# PRY397.net
KiCad netlist of a schematic drawn in EAGLE
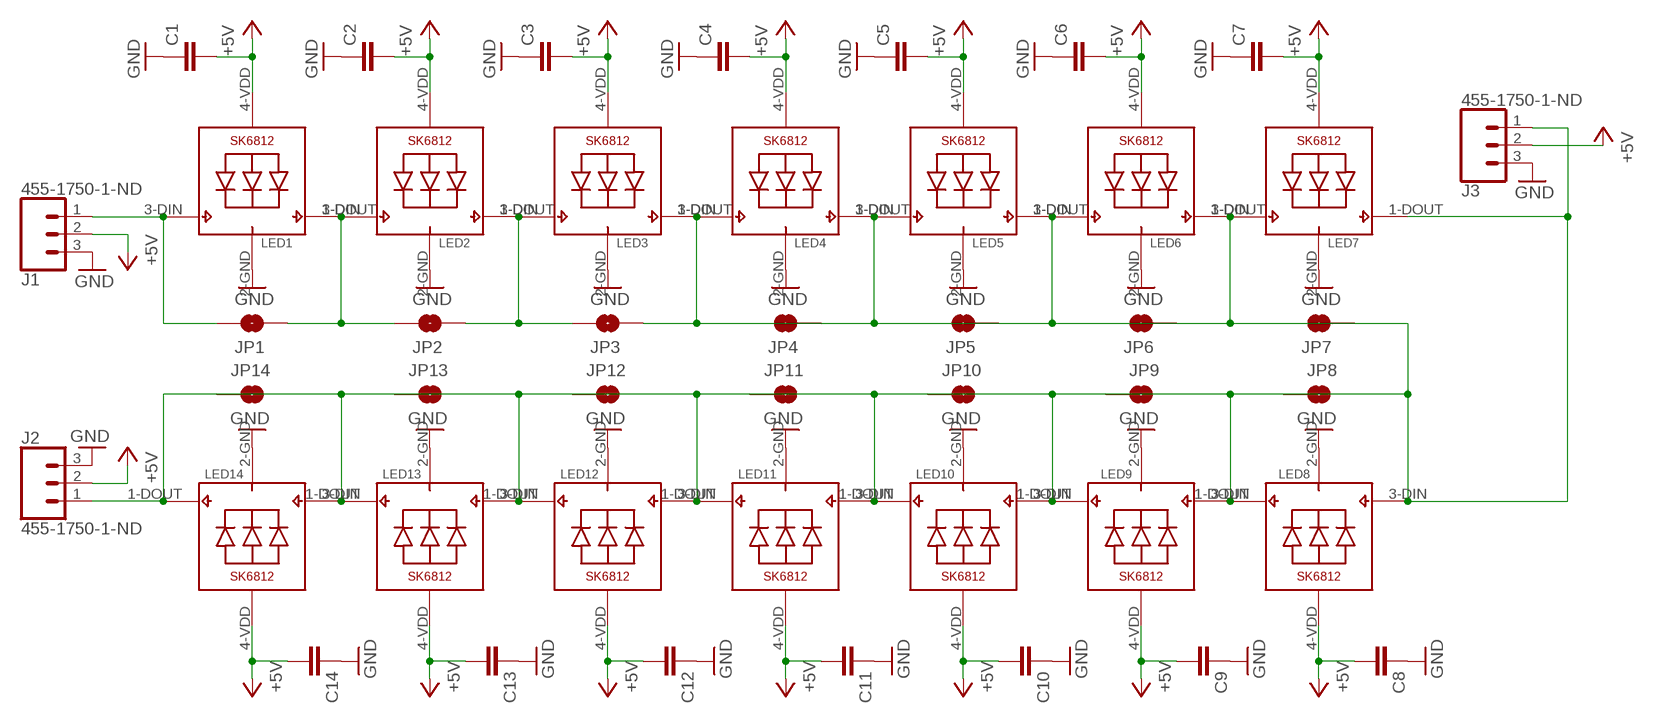
[diagram p0: schematic, sheet 1]

(export (version "E")
  (design (tool "Eeschema 10.0.6"))
  (components
    (comp (ref "C1")
      (value "C-EUC1206")
      (footprint "eagle-import:C1206")
      (libsource (lib "eagle-import") (part "C-EUC1206"))
    )
    (comp (ref "C2")
      (value "C-EUC1206")
      (footprint "eagle-import:C1206")
      (libsource (lib "eagle-import") (part "C-EUC1206"))
    )
    (comp (ref "C3")
      (value "C-EUC1206")
      (footprint "eagle-import:C1206")
      (libsource (lib "eagle-import") (part "C-EUC1206"))
    )
    (comp (ref "C4")
      (value "C-EUC1206")
      (footprint "eagle-import:C1206")
      (libsource (lib "eagle-import") (part "C-EUC1206"))
    )
    (comp (ref "C5")
      (value "C-EUC1206")
      (footprint "eagle-import:C1206")
      (libsource (lib "eagle-import") (part "C-EUC1206"))
    )
    (comp (ref "C6")
      (value "C-EUC1206")
      (footprint "eagle-import:C1206")
      (libsource (lib "eagle-import") (part "C-EUC1206"))
    )
    (comp (ref "C7")
      (value "C-EUC1206")
      (footprint "eagle-import:C1206")
      (libsource (lib "eagle-import") (part "C-EUC1206"))
    )
    (comp (ref "C8")
      (value "C-EUC1206")
      (footprint "eagle-import:C1206")
      (libsource (lib "eagle-import") (part "C-EUC1206"))
    )
    (comp (ref "C9")
      (value "C-EUC1206")
      (footprint "eagle-import:C1206")
      (libsource (lib "eagle-import") (part "C-EUC1206"))
    )
    (comp (ref "C10")
      (value "C-EUC1206")
      (footprint "eagle-import:C1206")
      (libsource (lib "eagle-import") (part "C-EUC1206"))
    )
    (comp (ref "C11")
      (value "C-EUC1206")
      (footprint "eagle-import:C1206")
      (libsource (lib "eagle-import") (part "C-EUC1206"))
    )
    (comp (ref "C12")
      (value "C-EUC1206")
      (footprint "eagle-import:C1206")
      (libsource (lib "eagle-import") (part "C-EUC1206"))
    )
    (comp (ref "C13")
      (value "C-EUC1206")
      (footprint "eagle-import:C1206")
      (libsource (lib "eagle-import") (part "C-EUC1206"))
    )
    (comp (ref "C14")
      (value "C-EUC1206")
      (footprint "eagle-import:C1206")
      (libsource (lib "eagle-import") (part "C-EUC1206"))
    )
    (comp (ref "J1")
      (value "455-1750-1-ND")
      (footprint "eagle-import:1X03")
      (libsource (lib "eagle-import") (part "CONN_03"))
    )
    (comp (ref "J2")
      (value "455-1750-1-ND")
      (footprint "eagle-import:1X03")
      (libsource (lib "eagle-import") (part "CONN_03"))
    )
    (comp (ref "J3")
      (value "455-1750-1-ND")
      (footprint "eagle-import:1X03_LONGPADS")
      (libsource (lib "eagle-import") (part "CONN_03LONGPADS"))
    )
    (comp (ref "JP1")
      (value "JUMPER-SMT_2_NO_SILK")
      (footprint "eagle-import:SMT-JUMPER_2_NO_SILK")
      (libsource (lib "eagle-import") (part "JUMPER-SMT_2_NO_SILK"))
    )
    (comp (ref "JP2")
      (value "JUMPER-SMT_2_NO_SILK")
      (footprint "eagle-import:SMT-JUMPER_2_NO_SILK")
      (libsource (lib "eagle-import") (part "JUMPER-SMT_2_NO_SILK"))
    )
    (comp (ref "JP3")
      (value "JUMPER-SMT_2_NO_SILK")
      (footprint "eagle-import:SMT-JUMPER_2_NO_SILK")
      (libsource (lib "eagle-import") (part "JUMPER-SMT_2_NO_SILK"))
    )
    (comp (ref "JP4")
      (value "JUMPER-SMT_2_NO_SILK")
      (footprint "eagle-import:SMT-JUMPER_2_NO_SILK")
      (libsource (lib "eagle-import") (part "JUMPER-SMT_2_NO_SILK"))
    )
    (comp (ref "JP5")
      (value "JUMPER-SMT_2_NO_SILK")
      (footprint "eagle-import:SMT-JUMPER_2_NO_SILK")
      (libsource (lib "eagle-import") (part "JUMPER-SMT_2_NO_SILK"))
    )
    (comp (ref "JP6")
      (value "JUMPER-SMT_2_NO_SILK")
      (footprint "eagle-import:SMT-JUMPER_2_NO_SILK")
      (libsource (lib "eagle-import") (part "JUMPER-SMT_2_NO_SILK"))
    )
    (comp (ref "JP7")
      (value "JUMPER-SMT_2_NO_SILK")
      (footprint "eagle-import:SMT-JUMPER_2_NO_SILK")
      (libsource (lib "eagle-import") (part "JUMPER-SMT_2_NO_SILK"))
    )
    (comp (ref "JP8")
      (value "JUMPER-SMT_2_NO_SILK")
      (footprint "eagle-import:SMT-JUMPER_2_NO_SILK")
      (libsource (lib "eagle-import") (part "JUMPER-SMT_2_NO_SILK"))
    )
    (comp (ref "JP9")
      (value "JUMPER-SMT_2_NO_SILK")
      (footprint "eagle-import:SMT-JUMPER_2_NO_SILK")
      (libsource (lib "eagle-import") (part "JUMPER-SMT_2_NO_SILK"))
    )
    (comp (ref "JP10")
      (value "JUMPER-SMT_2_NO_SILK")
      (footprint "eagle-import:SMT-JUMPER_2_NO_SILK")
      (libsource (lib "eagle-import") (part "JUMPER-SMT_2_NO_SILK"))
    )
    (comp (ref "JP11")
      (value "JUMPER-SMT_2_NO_SILK")
      (footprint "eagle-import:SMT-JUMPER_2_NO_SILK")
      (libsource (lib "eagle-import") (part "JUMPER-SMT_2_NO_SILK"))
    )
    (comp (ref "JP12")
      (value "JUMPER-SMT_2_NO_SILK")
      (footprint "eagle-import:SMT-JUMPER_2_NO_SILK")
      (libsource (lib "eagle-import") (part "JUMPER-SMT_2_NO_SILK"))
    )
    (comp (ref "JP13")
      (value "JUMPER-SMT_2_NO_SILK")
      (footprint "eagle-import:SMT-JUMPER_2_NO_SILK")
      (libsource (lib "eagle-import") (part "JUMPER-SMT_2_NO_SILK"))
    )
    (comp (ref "JP14")
      (value "JUMPER-SMT_2_NO_SILK")
      (footprint "eagle-import:SMT-JUMPER_2_NO_SILK")
      (libsource (lib "eagle-import") (part "JUMPER-SMT_2_NO_SILK"))
    )
    (comp (ref "LED1")
      (value "SK6812_3535")
      (footprint "eagle-import:LED3535")
      (libsource (lib "eagle-import") (part "SK6812_3535"))
    )
    (comp (ref "LED2")
      (value "SK6812_3535")
      (footprint "eagle-import:LED3535")
      (libsource (lib "eagle-import") (part "SK6812_3535"))
    )
    (comp (ref "LED3")
      (value "SK6812_3535")
      (footprint "eagle-import:LED3535")
      (libsource (lib "eagle-import") (part "SK6812_3535"))
    )
    (comp (ref "LED4")
      (value "SK6812_3535")
      (footprint "eagle-import:LED3535")
      (libsource (lib "eagle-import") (part "SK6812_3535"))
    )
    (comp (ref "LED5")
      (value "SK6812_3535")
      (footprint "eagle-import:LED3535")
      (libsource (lib "eagle-import") (part "SK6812_3535"))
    )
    (comp (ref "LED6")
      (value "SK6812_3535")
      (footprint "eagle-import:LED3535")
      (libsource (lib "eagle-import") (part "SK6812_3535"))
    )
    (comp (ref "LED7")
      (value "SK6812_3535")
      (footprint "eagle-import:LED3535")
      (libsource (lib "eagle-import") (part "SK6812_3535"))
    )
    (comp (ref "LED8")
      (value "SK6812_3535")
      (footprint "eagle-import:LED3535")
      (libsource (lib "eagle-import") (part "SK6812_3535"))
    )
    (comp (ref "LED9")
      (value "SK6812_3535")
      (footprint "eagle-import:LED3535")
      (libsource (lib "eagle-import") (part "SK6812_3535"))
    )
    (comp (ref "LED10")
      (value "SK6812_3535")
      (footprint "eagle-import:LED3535")
      (libsource (lib "eagle-import") (part "SK6812_3535"))
    )
    (comp (ref "LED11")
      (value "SK6812_3535")
      (footprint "eagle-import:LED3535")
      (libsource (lib "eagle-import") (part "SK6812_3535"))
    )
    (comp (ref "LED12")
      (value "SK6812_3535")
      (footprint "eagle-import:LED3535")
      (libsource (lib "eagle-import") (part "SK6812_3535"))
    )
    (comp (ref "LED13")
      (value "SK6812_3535")
      (footprint "eagle-import:LED3535")
      (libsource (lib "eagle-import") (part "SK6812_3535"))
    )
    (comp (ref "LED14")
      (value "SK6812_3535")
      (footprint "eagle-import:LED3535")
      (libsource (lib "eagle-import") (part "SK6812_3535"))
    )
  )
  (nets
    (net (code "1") (name "+5V") (class "Default")
      (node (ref "C1") (pin "2") (pinfunction "2_2") (pintype "passive"))
      (node (ref "C10") (pin "2") (pinfunction "2_2") (pintype "passive"))
      (node (ref "C11") (pin "2") (pinfunction "2_2") (pintype "passive"))
      (node (ref "C12") (pin "2") (pinfunction "2_2") (pintype "passive"))
      (node (ref "C13") (pin "2") (pinfunction "2_2") (pintype "passive"))
      (node (ref "C14") (pin "2") (pinfunction "2_2") (pintype "passive"))
      (node (ref "C2") (pin "2") (pinfunction "2_2") (pintype "passive"))
      (node (ref "C3") (pin "2") (pinfunction "2_2") (pintype "passive"))
      (node (ref "C4") (pin "2") (pinfunction "2_2") (pintype "passive"))
      (node (ref "C5") (pin "2") (pinfunction "2_2") (pintype "passive"))
      (node (ref "C6") (pin "2") (pinfunction "2_2") (pintype "passive"))
      (node (ref "C7") (pin "2") (pinfunction "2_2") (pintype "passive"))
      (node (ref "C8") (pin "2") (pinfunction "2_2") (pintype "passive"))
      (node (ref "C9") (pin "2") (pinfunction "2_2") (pintype "passive"))
      (node (ref "J1") (pin "2") (pinfunction "2_2") (pintype "passive"))
      (node (ref "J2") (pin "2") (pinfunction "2_2") (pintype "passive"))
      (node (ref "J3") (pin "2") (pinfunction "2_2") (pintype "passive"))
      (node (ref "LED1") (pin "4-VDD") (pinfunction "VDD_4-VDD") (pintype "power_in"))
      (node (ref "LED10") (pin "4-VDD") (pinfunction "VDD_4-VDD") (pintype "power_in"))
      (node (ref "LED11") (pin "4-VDD") (pinfunction "VDD_4-VDD") (pintype "power_in"))
      (node (ref "LED12") (pin "4-VDD") (pinfunction "VDD_4-VDD") (pintype "power_in"))
      (node (ref "LED13") (pin "4-VDD") (pinfunction "VDD_4-VDD") (pintype "power_in"))
      (node (ref "LED14") (pin "4-VDD") (pinfunction "VDD_4-VDD") (pintype "power_in"))
      (node (ref "LED2") (pin "4-VDD") (pinfunction "VDD_4-VDD") (pintype "power_in"))
      (node (ref "LED3") (pin "4-VDD") (pinfunction "VDD_4-VDD") (pintype "power_in"))
      (node (ref "LED4") (pin "4-VDD") (pinfunction "VDD_4-VDD") (pintype "power_in"))
      (node (ref "LED5") (pin "4-VDD") (pinfunction "VDD_4-VDD") (pintype "power_in"))
      (node (ref "LED6") (pin "4-VDD") (pinfunction "VDD_4-VDD") (pintype "power_in"))
      (node (ref "LED7") (pin "4-VDD") (pinfunction "VDD_4-VDD") (pintype "power_in"))
      (node (ref "LED8") (pin "4-VDD") (pinfunction "VDD_4-VDD") (pintype "power_in"))
      (node (ref "LED9") (pin "4-VDD") (pinfunction "VDD_4-VDD") (pintype "power_in"))
    )
    (net (code "2") (name "GND") (class "Default")
      (node (ref "C1") (pin "1") (pinfunction "1_1") (pintype "passive"))
      (node (ref "C10") (pin "1") (pinfunction "1_1") (pintype "passive"))
      (node (ref "C11") (pin "1") (pinfunction "1_1") (pintype "passive"))
      (node (ref "C12") (pin "1") (pinfunction "1_1") (pintype "passive"))
      (node (ref "C13") (pin "1") (pinfunction "1_1") (pintype "passive"))
      (node (ref "C14") (pin "1") (pinfunction "1_1") (pintype "passive"))
      (node (ref "C2") (pin "1") (pinfunction "1_1") (pintype "passive"))
      (node (ref "C3") (pin "1") (pinfunction "1_1") (pintype "passive"))
      (node (ref "C4") (pin "1") (pinfunction "1_1") (pintype "passive"))
      (node (ref "C5") (pin "1") (pinfunction "1_1") (pintype "passive"))
      (node (ref "C6") (pin "1") (pinfunction "1_1") (pintype "passive"))
      (node (ref "C7") (pin "1") (pinfunction "1_1") (pintype "passive"))
      (node (ref "C8") (pin "1") (pinfunction "1_1") (pintype "passive"))
      (node (ref "C9") (pin "1") (pinfunction "1_1") (pintype "passive"))
      (node (ref "J1") (pin "3") (pinfunction "3_3") (pintype "passive"))
      (node (ref "J2") (pin "3") (pinfunction "3_3") (pintype "passive"))
      (node (ref "J3") (pin "3") (pinfunction "3_3") (pintype "passive"))
      (node (ref "LED1") (pin "2-GND") (pinfunction "GND_2-GND") (pintype "power_in"))
      (node (ref "LED10") (pin "2-GND") (pinfunction "GND_2-GND") (pintype "power_in"))
      (node (ref "LED11") (pin "2-GND") (pinfunction "GND_2-GND") (pintype "power_in"))
      (node (ref "LED12") (pin "2-GND") (pinfunction "GND_2-GND") (pintype "power_in"))
      (node (ref "LED13") (pin "2-GND") (pinfunction "GND_2-GND") (pintype "power_in"))
      (node (ref "LED14") (pin "2-GND") (pinfunction "GND_2-GND") (pintype "power_in"))
      (node (ref "LED2") (pin "2-GND") (pinfunction "GND_2-GND") (pintype "power_in"))
      (node (ref "LED3") (pin "2-GND") (pinfunction "GND_2-GND") (pintype "power_in"))
      (node (ref "LED4") (pin "2-GND") (pinfunction "GND_2-GND") (pintype "power_in"))
      (node (ref "LED5") (pin "2-GND") (pinfunction "GND_2-GND") (pintype "power_in"))
      (node (ref "LED6") (pin "2-GND") (pinfunction "GND_2-GND") (pintype "power_in"))
      (node (ref "LED7") (pin "2-GND") (pinfunction "GND_2-GND") (pintype "power_in"))
      (node (ref "LED8") (pin "2-GND") (pinfunction "GND_2-GND") (pintype "power_in"))
      (node (ref "LED9") (pin "2-GND") (pinfunction "GND_2-GND") (pintype "power_in"))
    )
    (net (code "3") (name "Net-(LED1-DI)") (class "Default")
      (node (ref "J1") (pin "1") (pinfunction "1_1") (pintype "passive"))
      (node (ref "JP1") (pin "1") (pinfunction "1_1") (pintype "passive"))
      (node (ref "LED1") (pin "3-DIN") (pinfunction "DI_3-DIN") (pintype "input"))
    )
    (net (code "4") (name "Net-(LED1-DO)") (class "Default")
      (node (ref "JP1") (pin "2") (pinfunction "2_2") (pintype "passive"))
      (node (ref "JP2") (pin "1") (pinfunction "1_1") (pintype "passive"))
      (node (ref "LED1") (pin "1-DOUT") (pinfunction "DO_1-DOUT") (pintype "output"))
      (node (ref "LED2") (pin "3-DIN") (pinfunction "DI_3-DIN") (pintype "input"))
    )
    (net (code "5") (name "Net-(LED2-DO)") (class "Default")
      (node (ref "JP2") (pin "2") (pinfunction "2_2") (pintype "passive"))
      (node (ref "JP3") (pin "1") (pinfunction "1_1") (pintype "passive"))
      (node (ref "LED2") (pin "1-DOUT") (pinfunction "DO_1-DOUT") (pintype "output"))
      (node (ref "LED3") (pin "3-DIN") (pinfunction "DI_3-DIN") (pintype "input"))
    )
    (net (code "6") (name "Net-(LED3-DO)") (class "Default")
      (node (ref "JP3") (pin "2") (pinfunction "2_2") (pintype "passive"))
      (node (ref "JP4") (pin "2") (pinfunction "2_2") (pintype "passive"))
      (node (ref "LED3") (pin "1-DOUT") (pinfunction "DO_1-DOUT") (pintype "output"))
      (node (ref "LED4") (pin "3-DIN") (pinfunction "DI_3-DIN") (pintype "input"))
    )
    (net (code "7") (name "Net-(LED4-DO)") (class "Default")
      (node (ref "JP4") (pin "1") (pinfunction "1_1") (pintype "passive"))
      (node (ref "JP5") (pin "2") (pinfunction "2_2") (pintype "passive"))
      (node (ref "LED4") (pin "1-DOUT") (pinfunction "DO_1-DOUT") (pintype "output"))
      (node (ref "LED5") (pin "3-DIN") (pinfunction "DI_3-DIN") (pintype "input"))
    )
    (net (code "8") (name "Net-(LED5-DO)") (class "Default")
      (node (ref "JP5") (pin "1") (pinfunction "1_1") (pintype "passive"))
      (node (ref "JP6") (pin "2") (pinfunction "2_2") (pintype "passive"))
      (node (ref "LED5") (pin "1-DOUT") (pinfunction "DO_1-DOUT") (pintype "output"))
      (node (ref "LED6") (pin "3-DIN") (pinfunction "DI_3-DIN") (pintype "input"))
    )
    (net (code "9") (name "Net-(LED6-DO)") (class "Default")
      (node (ref "JP6") (pin "1") (pinfunction "1_1") (pintype "passive"))
      (node (ref "JP7") (pin "2") (pinfunction "2_2") (pintype "passive"))
      (node (ref "LED6") (pin "1-DOUT") (pinfunction "DO_1-DOUT") (pintype "output"))
      (node (ref "LED7") (pin "3-DIN") (pinfunction "DI_3-DIN") (pintype "input"))
    )
    (net (code "10") (name "Net-(LED7-DO)") (class "Default")
      (node (ref "J3") (pin "1") (pinfunction "1_1") (pintype "passive"))
      (node (ref "JP7") (pin "1") (pinfunction "1_1") (pintype "passive"))
      (node (ref "JP8") (pin "2") (pinfunction "2_2") (pintype "passive"))
      (node (ref "LED7") (pin "1-DOUT") (pinfunction "DO_1-DOUT") (pintype "output"))
      (node (ref "LED8") (pin "3-DIN") (pinfunction "DI_3-DIN") (pintype "input"))
    )
    (net (code "11") (name "Net-(LED8-DO)") (class "Default")
      (node (ref "JP8") (pin "1") (pinfunction "1_1") (pintype "passive"))
      (node (ref "JP9") (pin "2") (pinfunction "2_2") (pintype "passive"))
      (node (ref "LED8") (pin "1-DOUT") (pinfunction "DO_1-DOUT") (pintype "output"))
      (node (ref "LED9") (pin "3-DIN") (pinfunction "DI_3-DIN") (pintype "input"))
    )
    (net (code "12") (name "Net-(LED10-DI)") (class "Default")
      (node (ref "JP10") (pin "2") (pinfunction "2_2") (pintype "passive"))
      (node (ref "JP9") (pin "1") (pinfunction "1_1") (pintype "passive"))
      (node (ref "LED10") (pin "3-DIN") (pinfunction "DI_3-DIN") (pintype "input"))
      (node (ref "LED9") (pin "1-DOUT") (pinfunction "DO_1-DOUT") (pintype "output"))
    )
    (net (code "13") (name "Net-(LED10-DO)") (class "Default")
      (node (ref "JP10") (pin "1") (pinfunction "1_1") (pintype "passive"))
      (node (ref "JP11") (pin "2") (pinfunction "2_2") (pintype "passive"))
      (node (ref "LED10") (pin "1-DOUT") (pinfunction "DO_1-DOUT") (pintype "output"))
      (node (ref "LED11") (pin "3-DIN") (pinfunction "DI_3-DIN") (pintype "input"))
    )
    (net (code "14") (name "Net-(LED11-DO)") (class "Default")
      (node (ref "JP11") (pin "1") (pinfunction "1_1") (pintype "passive"))
      (node (ref "JP12") (pin "2") (pinfunction "2_2") (pintype "passive"))
      (node (ref "LED11") (pin "1-DOUT") (pinfunction "DO_1-DOUT") (pintype "output"))
      (node (ref "LED12") (pin "3-DIN") (pinfunction "DI_3-DIN") (pintype "input"))
    )
    (net (code "15") (name "Net-(LED12-DO)") (class "Default")
      (node (ref "JP12") (pin "1") (pinfunction "1_1") (pintype "passive"))
      (node (ref "JP13") (pin "2") (pinfunction "2_2") (pintype "passive"))
      (node (ref "LED12") (pin "1-DOUT") (pinfunction "DO_1-DOUT") (pintype "output"))
      (node (ref "LED13") (pin "3-DIN") (pinfunction "DI_3-DIN") (pintype "input"))
    )
    (net (code "16") (name "Net-(LED13-DO)") (class "Default")
      (node (ref "JP13") (pin "1") (pinfunction "1_1") (pintype "passive"))
      (node (ref "JP14") (pin "2") (pinfunction "2_2") (pintype "passive"))
      (node (ref "LED13") (pin "1-DOUT") (pinfunction "DO_1-DOUT") (pintype "output"))
      (node (ref "LED14") (pin "3-DIN") (pinfunction "DI_3-DIN") (pintype "input"))
    )
    (net (code "17") (name "Net-(LED14-DO)") (class "Default")
      (node (ref "J2") (pin "1") (pinfunction "1_1") (pintype "passive"))
      (node (ref "JP14") (pin "1") (pinfunction "1_1") (pintype "passive"))
      (node (ref "LED14") (pin "1-DOUT") (pinfunction "DO_1-DOUT") (pintype "output"))
    )
  )
)
